# Etch_a_Sketch.net
KiCad netlist of a schematic drawn in EAGLE
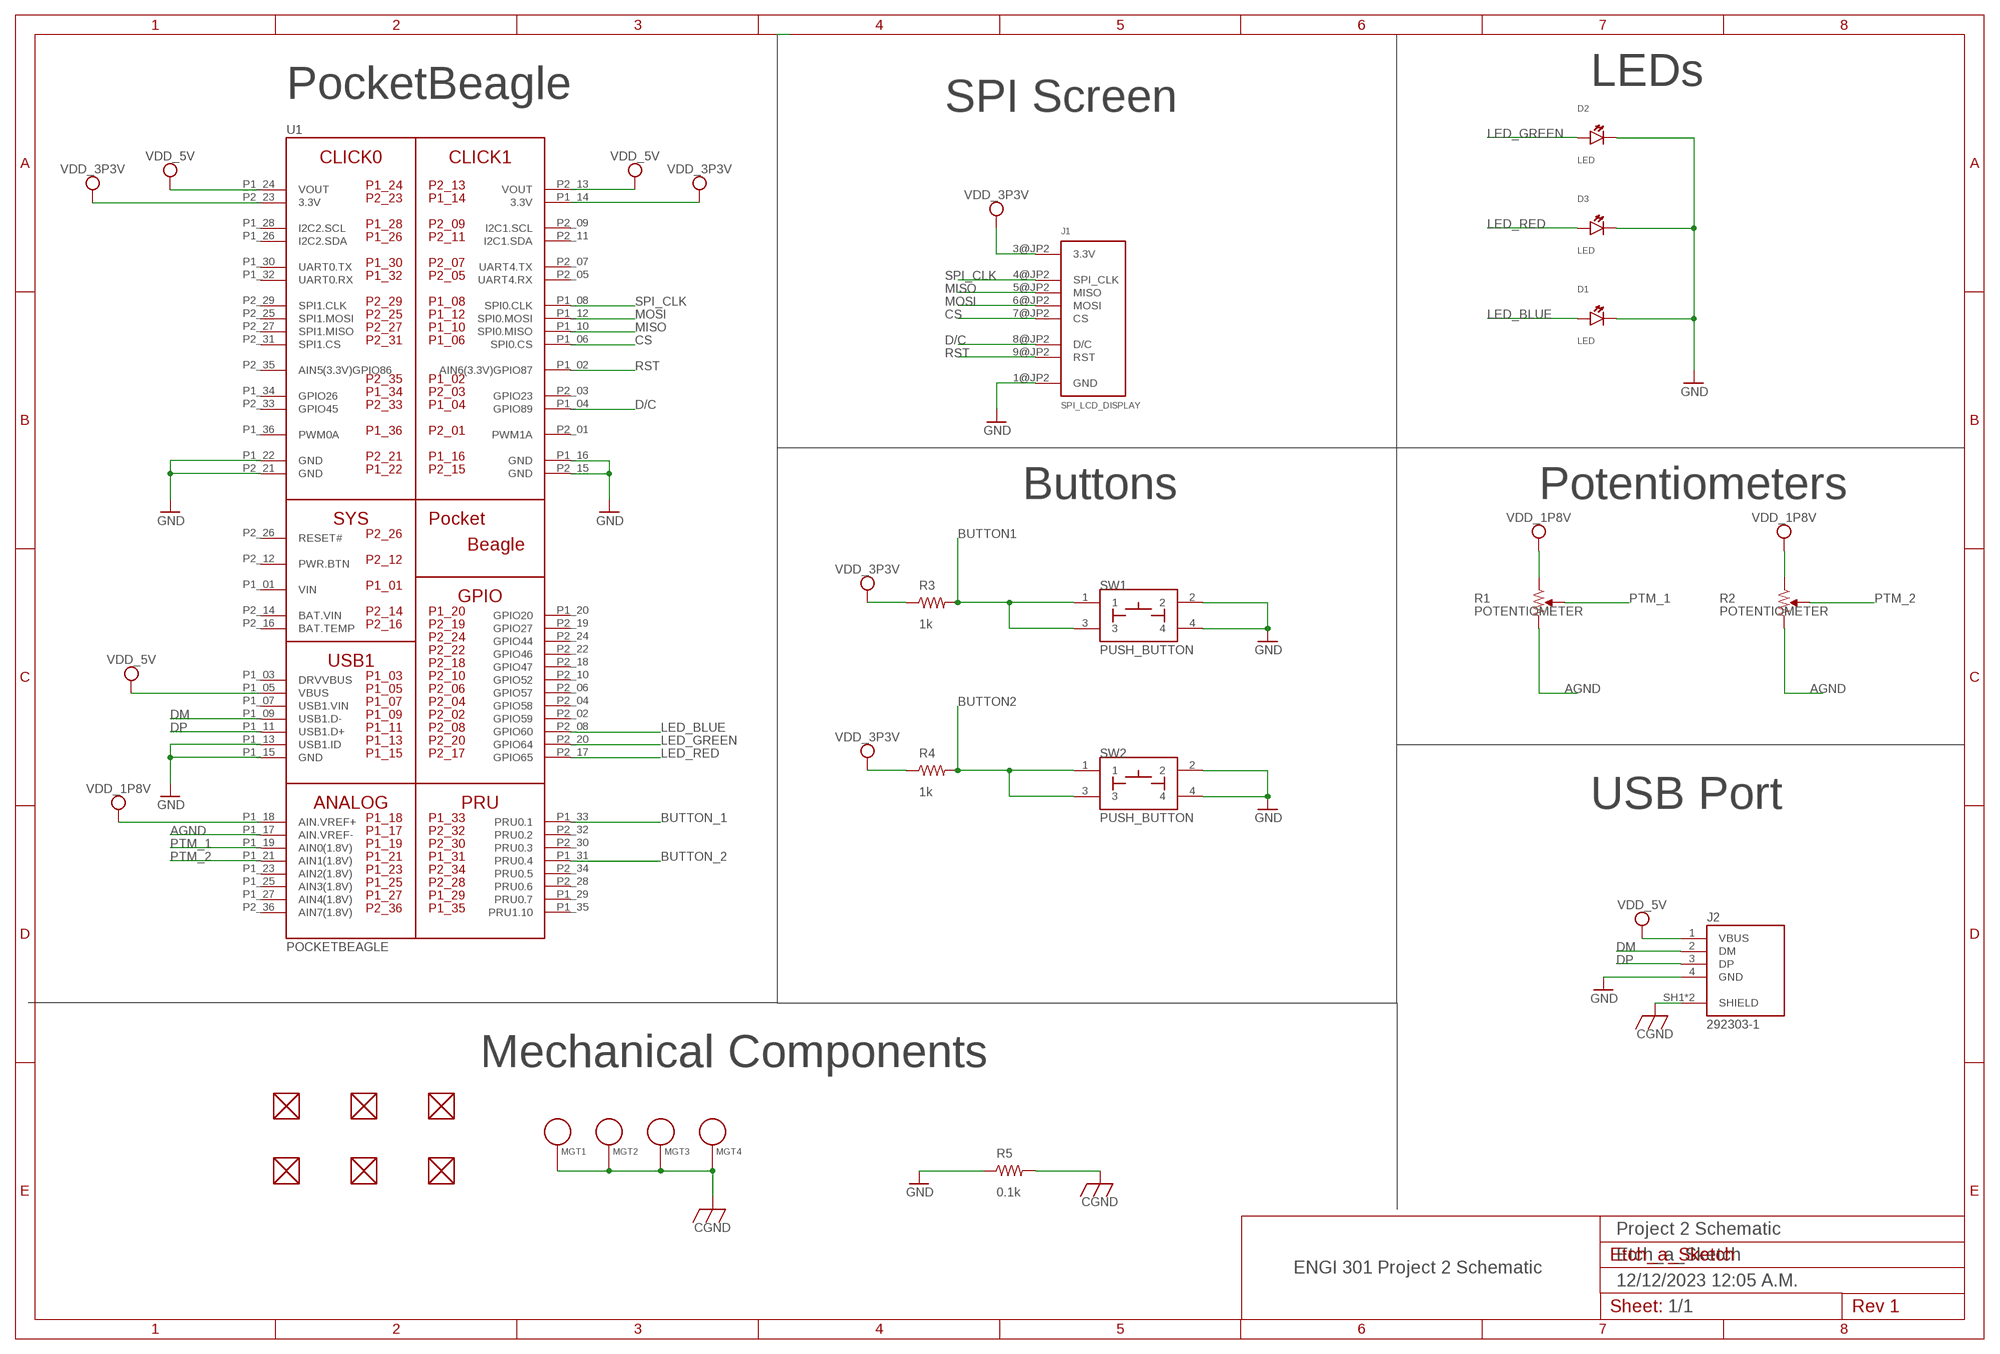
[diagram p0: schematic, sheet 1]

(export (version "E")
  (design (tool "Eeschema 10.0.6"))
  (components
    (comp (ref "D1")
      (value "LED")
      (footprint "eagle-import:EIA-STD")
      (libsource (lib "eagle-import") (part "LED"))
    )
    (comp (ref "D2")
      (value "LED")
      (footprint "eagle-import:EIA-STD")
      (libsource (lib "eagle-import") (part "LED"))
    )
    (comp (ref "D3")
      (value "LED")
      (footprint "eagle-import:EIA-STD")
      (libsource (lib "eagle-import") (part "LED"))
    )
    (comp (ref "FUD1")
      (value "FIDUCIAL")
      (footprint "eagle-import:FIDUCIAL_40MIL")
      (libsource (lib "eagle-import") (part "FIDUCIAL"))
    )
    (comp (ref "FUD2")
      (value "FIDUCIAL")
      (footprint "eagle-import:FIDUCIAL_40MIL")
      (libsource (lib "eagle-import") (part "FIDUCIAL"))
    )
    (comp (ref "FUD3")
      (value "FIDUCIAL")
      (footprint "eagle-import:FIDUCIAL_40MIL")
      (libsource (lib "eagle-import") (part "FIDUCIAL"))
    )
    (comp (ref "FUD4")
      (value "FIDUCIAL")
      (footprint "eagle-import:FIDUCIAL_40MIL")
      (libsource (lib "eagle-import") (part "FIDUCIAL"))
    )
    (comp (ref "FUD5")
      (value "FIDUCIAL")
      (footprint "eagle-import:FIDUCIAL_40MIL")
      (libsource (lib "eagle-import") (part "FIDUCIAL"))
    )
    (comp (ref "FUD6")
      (value "FIDUCIAL")
      (footprint "eagle-import:FIDUCIAL_40MIL")
      (libsource (lib "eagle-import") (part "FIDUCIAL"))
    )
    (comp (ref "J1")
      (value "SPI_LCD_DISPLAY")
      (footprint "eagle-import:SPI_LCD_DISPLAY")
      (libsource (lib "eagle-import") (part "SPI_LCD_DISPLAY"))
    )
    (comp (ref "J2")
      (value "292303-1")
      (footprint "eagle-import:TE_292303-1")
      (fields (field (name "MF") "TE Connectivity"))
      (libsource (lib "eagle-import") (part "292303-1"))
    )
    (comp (ref "MGT1")
      (value "MOUNTING_HOLE")
      (footprint "eagle-import:MOUNTING_HOLE")
      (libsource (lib "eagle-import") (part "MOUNTING_HOLE"))
    )
    (comp (ref "MGT2")
      (value "MOUNTING_HOLE")
      (footprint "eagle-import:MOUNTING_HOLE")
      (libsource (lib "eagle-import") (part "MOUNTING_HOLE"))
    )
    (comp (ref "MGT3")
      (value "MOUNTING_HOLE")
      (footprint "eagle-import:MOUNTING_HOLE")
      (libsource (lib "eagle-import") (part "MOUNTING_HOLE"))
    )
    (comp (ref "MGT4")
      (value "MOUNTING_HOLE")
      (footprint "eagle-import:MOUNTING_HOLE")
      (libsource (lib "eagle-import") (part "MOUNTING_HOLE"))
    )
    (comp (ref "R1")
      (value "POTENTIOMETER")
      (footprint "eagle-import:POT-PO90S")
      (libsource (lib "eagle-import") (part "POTENTIOMETER"))
    )
    (comp (ref "R2")
      (value "POTENTIOMETER")
      (footprint "eagle-import:POT-PO90S")
      (libsource (lib "eagle-import") (part "POTENTIOMETER"))
    )
    (comp (ref "R3")
      (value "1k")
      (footprint "eagle-import:R0603")
      (libsource (lib "eagle-import") (part "R_R0603"))
    )
    (comp (ref "R4")
      (value "1k")
      (footprint "eagle-import:R0603")
      (libsource (lib "eagle-import") (part "R_R0603"))
    )
    (comp (ref "R5")
      (value "0.1k")
      (footprint "eagle-import:R0603")
      (libsource (lib "eagle-import") (part "R_R0603"))
    )
    (comp (ref "SW1")
      (value "PUSH_BUTTON")
      (footprint "eagle-import:BUTTON_12.5MM")
      (libsource (lib "eagle-import") (part "PUSH_BUTTON"))
    )
    (comp (ref "SW2")
      (value "PUSH_BUTTON")
      (footprint "eagle-import:BUTTON_12.5MM")
      (libsource (lib "eagle-import") (part "PUSH_BUTTON"))
    )
    (comp (ref "U1")
      (value "POCKETBEAGLE")
      (footprint "eagle-import:POCKETBEAGLE")
      (libsource (lib "eagle-import") (part "POCKETBEAGLE"))
    )
  )
  (nets
    (net (code "1") (name "/AGND") (class "Default")
      (node (ref "R1") (pin "CW") (pinfunction "CW_CW") (pintype "passive"))
      (node (ref "R2") (pin "CW") (pinfunction "CW_CW") (pintype "passive"))
      (node (ref "U1") (pin "P1_17") (pinfunction "AIN.VREF-_P1_17") (pintype "input"))
    )
    (net (code "2") (name "/BAT.VIN") (class "Default")
      (node (ref "U1") (pin "P2_14") (pinfunction "BAT.VIN_P2_14") (pintype "power_in"))
    )
    (net (code "3") (name "/BUTTON1") (class "Default")
      (node (ref "R3") (pin "2") (pinfunction "2_2") (pintype "passive"))
      (node (ref "SW1") (pin "1") (pinfunction "1_1") (pintype "bidirectional"))
      (node (ref "SW1") (pin "3") (pinfunction "3_3") (pintype "bidirectional"))
    )
    (net (code "4") (name "/BUTTON2") (class "Default")
      (node (ref "R4") (pin "2") (pinfunction "2_2") (pintype "passive"))
      (node (ref "SW2") (pin "1") (pinfunction "1_1") (pintype "bidirectional"))
      (node (ref "SW2") (pin "3") (pinfunction "3_3") (pintype "bidirectional"))
    )
    (net (code "5") (name "/BUTTON_1") (class "Default")
      (node (ref "U1") (pin "P1_33") (pinfunction "PRU0.1_P1_33") (pintype "bidirectional"))
    )
    (net (code "6") (name "/BUTTON_2") (class "Default")
      (node (ref "U1") (pin "P1_31") (pinfunction "PRU0.4_P1_31") (pintype "bidirectional"))
    )
    (net (code "7") (name "/CS") (class "Default")
      (node (ref "J1") (pin "7@JP2") (pinfunction "CS_7@JP2") (pintype "bidirectional"))
      (node (ref "U1") (pin "P1_06") (pinfunction "SPI0.CS_P1_06") (pintype "bidirectional"))
    )
    (net (code "8") (name "/DM") (class "Default")
      (node (ref "J2") (pin "2") (pinfunction "DM_2") (pintype "passive"))
      (node (ref "U1") (pin "P1_09") (pinfunction "USB1.D-_P1_09") (pintype "bidirectional"))
    )
    (net (code "9") (name "/DP") (class "Default")
      (node (ref "J2") (pin "3") (pinfunction "DP_3") (pintype "passive"))
      (node (ref "U1") (pin "P1_11") (pinfunction "USB1.D+_P1_11") (pintype "bidirectional"))
    )
    (net (code "10") (name "/D{slash}C") (class "Default")
      (node (ref "J1") (pin "8@JP2") (pinfunction "D/C_8@JP2") (pintype "bidirectional"))
      (node (ref "U1") (pin "P1_04") (pinfunction "GPIO89_P1_04") (pintype "bidirectional"))
    )
    (net (code "11") (name "/LED_BLUE") (class "Default")
      (node (ref "D1") (pin "ANODE") (pinfunction "ANODE_ANODE") (pintype "bidirectional"))
      (node (ref "U1") (pin "P2_08") (pinfunction "GPIO60_P2_08") (pintype "bidirectional"))
    )
    (net (code "12") (name "/LED_GREEN") (class "Default")
      (node (ref "D2") (pin "ANODE") (pinfunction "ANODE_ANODE") (pintype "bidirectional"))
      (node (ref "U1") (pin "P2_20") (pinfunction "GPIO64_P2_20") (pintype "bidirectional"))
    )
    (net (code "13") (name "/LED_RED") (class "Default")
      (node (ref "D3") (pin "ANODE") (pinfunction "ANODE_ANODE") (pintype "bidirectional"))
      (node (ref "U1") (pin "P2_17") (pinfunction "GPIO65_P2_17") (pintype "bidirectional"))
    )
    (net (code "14") (name "/MISO") (class "Default")
      (node (ref "J1") (pin "5@JP2") (pinfunction "MISO_5@JP2") (pintype "bidirectional"))
      (node (ref "U1") (pin "P1_10") (pinfunction "SPI0.MISO_P1_10") (pintype "bidirectional"))
    )
    (net (code "15") (name "/MOSI") (class "Default")
      (node (ref "J1") (pin "6@JP2") (pinfunction "MOSI_6@JP2") (pintype "bidirectional"))
      (node (ref "U1") (pin "P1_12") (pinfunction "SPI0.MOSI_P1_12") (pintype "bidirectional"))
    )
    (net (code "16") (name "/PTM_1") (class "Default")
      (node (ref "R1") (pin "S") (pinfunction "S_S") (pintype "bidirectional"))
      (node (ref "U1") (pin "P1_19") (pinfunction "AIN0(1.8V)_P1_19") (pintype "input"))
    )
    (net (code "17") (name "/PTM_2") (class "Default")
      (node (ref "R2") (pin "S") (pinfunction "S_S") (pintype "bidirectional"))
      (node (ref "U1") (pin "P1_21") (pinfunction "AIN1(1.8V)_P1_21") (pintype "input"))
    )
    (net (code "18") (name "/RST") (class "Default")
      (node (ref "J1") (pin "9@JP2") (pinfunction "RST_9@JP2") (pintype "bidirectional"))
      (node (ref "U1") (pin "P1_02") (pinfunction "AIN6(3.3V)GPIO87_P1_02") (pintype "bidirectional"))
    )
    (net (code "19") (name "/SPI_CLK") (class "Default")
      (node (ref "J1") (pin "4@JP2") (pinfunction "SPI_CLK_4@JP2") (pintype "bidirectional"))
      (node (ref "U1") (pin "P1_08") (pinfunction "SPI0.CLK_P1_08") (pintype "bidirectional"))
    )
    (net (code "20") (name "/VIN") (class "Default")
      (node (ref "U1") (pin "P1_01") (pinfunction "VIN_P1_01") (pintype "power_in"))
    )
    (net (code "21") (name "CGND") (class "Default")
      (node (ref "J2") (pin "SH1") (pinfunction "SHIELD_SH1") (pintype "passive"))
      (node (ref "J2") (pin "SH2") (pinfunction "SHIELD_SH2") (pintype "passive"))
      (node (ref "MGT1") (pin "P$1") (pinfunction "P$1_P$1") (pintype "bidirectional"))
      (node (ref "MGT2") (pin "P$1") (pinfunction "P$1_P$1") (pintype "bidirectional"))
      (node (ref "MGT3") (pin "P$1") (pinfunction "P$1_P$1") (pintype "bidirectional"))
      (node (ref "MGT4") (pin "P$1") (pinfunction "P$1_P$1") (pintype "bidirectional"))
      (node (ref "R5") (pin "2") (pinfunction "2_2") (pintype "passive"))
    )
    (net (code "22") (name "GND") (class "Default")
      (node (ref "D1") (pin "CATHODE") (pinfunction "CATHODE_CATHODE") (pintype "bidirectional"))
      (node (ref "D2") (pin "CATHODE") (pinfunction "CATHODE_CATHODE") (pintype "bidirectional"))
      (node (ref "D3") (pin "CATHODE") (pinfunction "CATHODE_CATHODE") (pintype "bidirectional"))
      (node (ref "J1") (pin "1@JP2") (pinfunction "GND_1@JP2") (pintype "bidirectional"))
      (node (ref "J2") (pin "4") (pinfunction "GND_4") (pintype "passive"))
      (node (ref "R5") (pin "1") (pinfunction "1_1") (pintype "passive"))
      (node (ref "SW1") (pin "2") (pinfunction "2_2") (pintype "bidirectional"))
      (node (ref "SW1") (pin "4") (pinfunction "4_4") (pintype "bidirectional"))
      (node (ref "SW2") (pin "2") (pinfunction "2_2") (pintype "bidirectional"))
      (node (ref "SW2") (pin "4") (pinfunction "4_4") (pintype "bidirectional"))
      (node (ref "U1") (pin "P1_13") (pinfunction "USB1.ID_P1_13") (pintype "bidirectional"))
      (node (ref "U1") (pin "P1_15") (pinfunction "GND_P1_15") (pintype "bidirectional"))
      (node (ref "U1") (pin "P1_16") (pinfunction "GND_P1_16") (pintype "power_in"))
      (node (ref "U1") (pin "P1_22") (pinfunction "GND_P1_22") (pintype "power_in"))
      (node (ref "U1") (pin "P2_15") (pinfunction "GND_P2_15") (pintype "power_in"))
      (node (ref "U1") (pin "P2_21") (pinfunction "GND_P2_21") (pintype "power_in"))
    )
    (net (code "23") (name "VDD_1P8V") (class "Default")
      (node (ref "R1") (pin "CCW") (pinfunction "CCW_CCW") (pintype "passive"))
      (node (ref "R2") (pin "CCW") (pinfunction "CCW_CCW") (pintype "passive"))
      (node (ref "U1") (pin "P1_18") (pinfunction "AIN.VREF+_P1_18") (pintype "input"))
    )
    (net (code "24") (name "VDD_3P3V") (class "Default")
      (node (ref "J1") (pin "3@JP2") (pinfunction "3.3V_3@JP2") (pintype "bidirectional"))
      (node (ref "R3") (pin "1") (pinfunction "1_1") (pintype "passive"))
      (node (ref "R4") (pin "1") (pinfunction "1_1") (pintype "passive"))
      (node (ref "U1") (pin "P1_14") (pinfunction "3.3V_P1_14") (pintype "power_in"))
      (node (ref "U1") (pin "P2_23") (pinfunction "3.3V_P2_23") (pintype "power_in"))
    )
    (net (code "25") (name "VDD_5V") (class "Default")
      (node (ref "J2") (pin "1") (pinfunction "VBUS_1") (pintype "passive"))
      (node (ref "U1") (pin "P1_05") (pinfunction "VBUS_P1_05") (pintype "bidirectional"))
      (node (ref "U1") (pin "P1_24") (pinfunction "VOUT_P1_24") (pintype "power_in"))
      (node (ref "U1") (pin "P2_13") (pinfunction "VOUT_P2_13") (pintype "power_in"))
    )
    (net (code "26") (name "unconnected-(FUD1-PadP$1)") (class "Default")
      (node (ref "FUD1") (pin "P$1") (pinfunction "P$1_P$1") (pintype "no_connect"))
    )
    (net (code "27") (name "unconnected-(FUD2-PadP$1)") (class "Default")
      (node (ref "FUD2") (pin "P$1") (pinfunction "P$1_P$1") (pintype "no_connect"))
    )
    (net (code "28") (name "unconnected-(FUD3-PadP$1)") (class "Default")
      (node (ref "FUD3") (pin "P$1") (pinfunction "P$1_P$1") (pintype "no_connect"))
    )
    (net (code "29") (name "unconnected-(FUD4-PadP$1)") (class "Default")
      (node (ref "FUD4") (pin "P$1") (pinfunction "P$1_P$1") (pintype "no_connect"))
    )
    (net (code "30") (name "unconnected-(FUD5-PadP$1)") (class "Default")
      (node (ref "FUD5") (pin "P$1") (pinfunction "P$1_P$1") (pintype "no_connect"))
    )
    (net (code "31") (name "unconnected-(FUD6-PadP$1)") (class "Default")
      (node (ref "FUD6") (pin "P$1") (pinfunction "P$1_P$1") (pintype "no_connect"))
    )
    (net (code "32") (name "unconnected-(U1-AIN2(1.8V)-PadP1_23)") (class "Default")
      (node (ref "U1") (pin "P1_23") (pinfunction "AIN2(1.8V)_P1_23") (pintype "input"))
    )
    (net (code "33") (name "unconnected-(U1-AIN3(1.8V)-PadP1_25)") (class "Default")
      (node (ref "U1") (pin "P1_25") (pinfunction "AIN3(1.8V)_P1_25") (pintype "input"))
    )
    (net (code "34") (name "unconnected-(U1-AIN4(1.8V)-PadP1_27)") (class "Default")
      (node (ref "U1") (pin "P1_27") (pinfunction "AIN4(1.8V)_P1_27") (pintype "input"))
    )
    (net (code "35") (name "unconnected-(U1-AIN5(3.3V)GPIO86-PadP2_35)") (class "Default")
      (node (ref "U1") (pin "P2_35") (pinfunction "AIN5(3.3V)GPIO86_P2_35") (pintype "bidirectional"))
    )
    (net (code "36") (name "unconnected-(U1-AIN7(1.8V)-PadP2_36)") (class "Default")
      (node (ref "U1") (pin "P2_36") (pinfunction "AIN7(1.8V)_P2_36") (pintype "input"))
    )
    (net (code "37") (name "unconnected-(U1-BAT.TEMP-PadP2_16)") (class "Default")
      (node (ref "U1") (pin "P2_16") (pinfunction "BAT.TEMP_P2_16") (pintype "input"))
    )
    (net (code "38") (name "unconnected-(U1-DRVVBUS-PadP1_03)") (class "Default")
      (node (ref "U1") (pin "P1_03") (pinfunction "DRVVBUS_P1_03") (pintype "bidirectional"))
    )
    (net (code "39") (name "unconnected-(U1-GPIO20-PadP1_20)") (class "Default")
      (node (ref "U1") (pin "P1_20") (pinfunction "GPIO20_P1_20") (pintype "bidirectional"))
    )
    (net (code "40") (name "unconnected-(U1-GPIO23-PadP2_03)") (class "Default")
      (node (ref "U1") (pin "P2_03") (pinfunction "GPIO23_P2_03") (pintype "bidirectional"))
    )
    (net (code "41") (name "unconnected-(U1-GPIO26-PadP1_34)") (class "Default")
      (node (ref "U1") (pin "P1_34") (pinfunction "GPIO26_P1_34") (pintype "bidirectional"))
    )
    (net (code "42") (name "unconnected-(U1-GPIO27-PadP2_19)") (class "Default")
      (node (ref "U1") (pin "P2_19") (pinfunction "GPIO27_P2_19") (pintype "bidirectional"))
    )
    (net (code "43") (name "unconnected-(U1-GPIO44-PadP2_24)") (class "Default")
      (node (ref "U1") (pin "P2_24") (pinfunction "GPIO44_P2_24") (pintype "bidirectional"))
    )
    (net (code "44") (name "unconnected-(U1-GPIO45-PadP2_33)") (class "Default")
      (node (ref "U1") (pin "P2_33") (pinfunction "GPIO45_P2_33") (pintype "bidirectional"))
    )
    (net (code "45") (name "unconnected-(U1-GPIO46-PadP2_22)") (class "Default")
      (node (ref "U1") (pin "P2_22") (pinfunction "GPIO46_P2_22") (pintype "bidirectional"))
    )
    (net (code "46") (name "unconnected-(U1-GPIO47-PadP2_18)") (class "Default")
      (node (ref "U1") (pin "P2_18") (pinfunction "GPIO47_P2_18") (pintype "bidirectional"))
    )
    (net (code "47") (name "unconnected-(U1-GPIO52-PadP2_10)") (class "Default")
      (node (ref "U1") (pin "P2_10") (pinfunction "GPIO52_P2_10") (pintype "bidirectional"))
    )
    (net (code "48") (name "unconnected-(U1-GPIO57-PadP2_06)") (class "Default")
      (node (ref "U1") (pin "P2_06") (pinfunction "GPIO57_P2_06") (pintype "bidirectional"))
    )
    (net (code "49") (name "unconnected-(U1-GPIO58-PadP2_04)") (class "Default")
      (node (ref "U1") (pin "P2_04") (pinfunction "GPIO58_P2_04") (pintype "bidirectional"))
    )
    (net (code "50") (name "unconnected-(U1-GPIO59-PadP2_02)") (class "Default")
      (node (ref "U1") (pin "P2_02") (pinfunction "GPIO59_P2_02") (pintype "bidirectional"))
    )
    (net (code "51") (name "unconnected-(U1-I2C1.SCL-PadP2_09)") (class "Default")
      (node (ref "U1") (pin "P2_09") (pinfunction "I2C1.SCL_P2_09") (pintype "bidirectional"))
    )
    (net (code "52") (name "unconnected-(U1-I2C1.SDA-PadP2_11)") (class "Default")
      (node (ref "U1") (pin "P2_11") (pinfunction "I2C1.SDA_P2_11") (pintype "bidirectional"))
    )
    (net (code "53") (name "unconnected-(U1-I2C2.SCL-PadP1_28)") (class "Default")
      (node (ref "U1") (pin "P1_28") (pinfunction "I2C2.SCL_P1_28") (pintype "bidirectional"))
    )
    (net (code "54") (name "unconnected-(U1-I2C2.SDA-PadP1_26)") (class "Default")
      (node (ref "U1") (pin "P1_26") (pinfunction "I2C2.SDA_P1_26") (pintype "bidirectional"))
    )
    (net (code "55") (name "unconnected-(U1-PRU0.2-PadP2_32)") (class "Default")
      (node (ref "U1") (pin "P2_32") (pinfunction "PRU0.2_P2_32") (pintype "bidirectional"))
    )
    (net (code "56") (name "unconnected-(U1-PRU0.3-PadP2_30)") (class "Default")
      (node (ref "U1") (pin "P2_30") (pinfunction "PRU0.3_P2_30") (pintype "bidirectional"))
    )
    (net (code "57") (name "unconnected-(U1-PRU0.5-PadP2_34)") (class "Default")
      (node (ref "U1") (pin "P2_34") (pinfunction "PRU0.5_P2_34") (pintype "bidirectional"))
    )
    (net (code "58") (name "unconnected-(U1-PRU0.6-PadP2_28)") (class "Default")
      (node (ref "U1") (pin "P2_28") (pinfunction "PRU0.6_P2_28") (pintype "bidirectional"))
    )
    (net (code "59") (name "unconnected-(U1-PRU0.7-PadP1_29)") (class "Default")
      (node (ref "U1") (pin "P1_29") (pinfunction "PRU0.7_P1_29") (pintype "bidirectional"))
    )
    (net (code "60") (name "unconnected-(U1-PRU1.10-PadP1_35)") (class "Default")
      (node (ref "U1") (pin "P1_35") (pinfunction "PRU1.10_P1_35") (pintype "bidirectional"))
    )
    (net (code "61") (name "unconnected-(U1-PWM0A-PadP1_36)") (class "Default")
      (node (ref "U1") (pin "P1_36") (pinfunction "PWM0A_P1_36") (pintype "bidirectional"))
    )
    (net (code "62") (name "unconnected-(U1-PWM1A-PadP2_01)") (class "Default")
      (node (ref "U1") (pin "P2_01") (pinfunction "PWM1A_P2_01") (pintype "bidirectional"))
    )
    (net (code "63") (name "unconnected-(U1-PWR.BTN-PadP2_12)") (class "Default")
      (node (ref "U1") (pin "P2_12") (pinfunction "PWR.BTN_P2_12") (pintype "input"))
    )
    (net (code "64") (name "unconnected-(U1-RESET#-PadP2_26)") (class "Default")
      (node (ref "U1") (pin "P2_26") (pinfunction "RESET#_P2_26") (pintype "input"))
    )
    (net (code "65") (name "unconnected-(U1-SPI1.CLK-PadP2_29)") (class "Default")
      (node (ref "U1") (pin "P2_29") (pinfunction "SPI1.CLK_P2_29") (pintype "bidirectional"))
    )
    (net (code "66") (name "unconnected-(U1-SPI1.CS-PadP2_31)") (class "Default")
      (node (ref "U1") (pin "P2_31") (pinfunction "SPI1.CS_P2_31") (pintype "bidirectional"))
    )
    (net (code "67") (name "unconnected-(U1-SPI1.MISO-PadP2_27)") (class "Default")
      (node (ref "U1") (pin "P2_27") (pinfunction "SPI1.MISO_P2_27") (pintype "bidirectional"))
    )
    (net (code "68") (name "unconnected-(U1-SPI1.MOSI-PadP2_25)") (class "Default")
      (node (ref "U1") (pin "P2_25") (pinfunction "SPI1.MOSI_P2_25") (pintype "bidirectional"))
    )
    (net (code "69") (name "unconnected-(U1-UART0.RX-PadP1_32)") (class "Default")
      (node (ref "U1") (pin "P1_32") (pinfunction "UART0.RX_P1_32") (pintype "bidirectional"))
    )
    (net (code "70") (name "unconnected-(U1-UART0.TX-PadP1_30)") (class "Default")
      (node (ref "U1") (pin "P1_30") (pinfunction "UART0.TX_P1_30") (pintype "bidirectional"))
    )
    (net (code "71") (name "unconnected-(U1-UART4.RX-PadP2_05)") (class "Default")
      (node (ref "U1") (pin "P2_05") (pinfunction "UART4.RX_P2_05") (pintype "bidirectional"))
    )
    (net (code "72") (name "unconnected-(U1-UART4.TX-PadP2_07)") (class "Default")
      (node (ref "U1") (pin "P2_07") (pinfunction "UART4.TX_P2_07") (pintype "bidirectional"))
    )
    (net (code "73") (name "unconnected-(U1-USB1.VIN-PadP1_07)") (class "Default")
      (node (ref "U1") (pin "P1_07") (pinfunction "USB1.VIN_P1_07") (pintype "bidirectional"))
    )
  )
)
